# Current_prototype.net
KiCad netlist of a schematic drawn in EAGLE
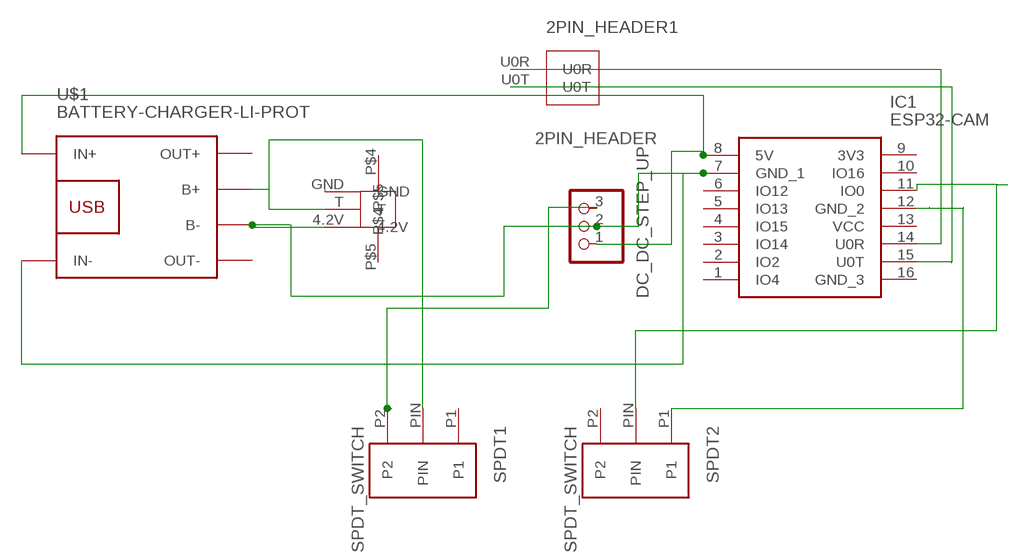
[diagram p0: schematic, sheet 1]

(export (version "E")
  (design (tool "Eeschema 10.0.6"))
  (components
    (comp (ref "2PIN_HEADER1")
      (value "2PIN_HEADER")
      (footprint "eagle-import:2PIN_HEADER")
      (libsource (lib "eagle-import") (part "2PIN_HEADER"))
    )
    (comp (ref "DC_DC_STEP_UP")
      (value "PINHD-1X3")
      (footprint "eagle-import:1X03")
      (libsource (lib "eagle-import") (part "PINHD-1X3"))
    )
    (comp (ref "IC1")
      (value "ESP32-CAM")
      (footprint "eagle-import:ESP32CAM")
      (libsource (lib "eagle-import") (part "ESP32-CAM"))
    )
    (comp (ref "SPDT1")
      (value "SPDT_SWITCH")
      (footprint "eagle-import:SPDT_SWITCH")
      (libsource (lib "eagle-import") (part "SPDT_SWITCH"))
    )
    (comp (ref "SPDT2")
      (value "SPDT_SWITCH")
      (footprint "eagle-import:SPDT_SWITCH")
      (libsource (lib "eagle-import") (part "SPDT_SWITCH"))
    )
    (comp (ref "U$1")
      (value "BATTERY-CHARGER-LI-PROT")
      (footprint "eagle-import:BATTERY-CHARGER-LI-PROT")
      (libsource (lib "eagle-import") (part "BATTERY-CHARGER-LI-PROT"))
    )
    (comp (ref "U$2")
      (value "BATTERY_CONNECTOR")
      (footprint "eagle-import:BATTERY_CONNECTOR")
      (libsource (lib "eagle-import") (part "BATTERY_CONNECTOR"))
    )
  )
  (nets
    (net (code "1") (name "Net-(DC_DC_STEP_UP-Pad3)") (class "Default")
      (node (ref "DC_DC_STEP_UP") (pin "3") (pinfunction "3_3") (pintype "passive"))
      (node (ref "SPDT1") (pin "P2") (pinfunction "P2_P2") (pintype "bidirectional"))
    )
    (net (code "2") (name "Net-(IC1-5V)") (class "Default")
      (node (ref "DC_DC_STEP_UP") (pin "1") (pinfunction "1_1") (pintype "passive"))
      (node (ref "IC1") (pin "8") (pinfunction "5V_8") (pintype "bidirectional"))
      (node (ref "U$1") (pin "IN+") (pinfunction "IN+_IN+") (pintype "bidirectional"))
    )
    (net (code "3") (name "Net-(IC1-GND_1)") (class "Default")
      (node (ref "DC_DC_STEP_UP") (pin "2") (pinfunction "2_2") (pintype "passive"))
      (node (ref "IC1") (pin "7") (pinfunction "GND_1_7") (pintype "bidirectional"))
      (node (ref "U$1") (pin "B-") (pinfunction "B-_B-") (pintype "bidirectional"))
      (node (ref "U$1") (pin "IN-") (pinfunction "IN-_IN-") (pintype "bidirectional"))
      (node (ref "U$2") (pin "4.2V") (pinfunction "4.2V_4.2V") (pintype "bidirectional"))
    )
    (net (code "4") (name "Net-(IC1-GND_2)") (class "Default")
      (node (ref "IC1") (pin "12") (pinfunction "GND_2_12") (pintype "bidirectional"))
      (node (ref "SPDT2") (pin "P1") (pinfunction "P1_P1") (pintype "bidirectional"))
    )
    (net (code "5") (name "Net-(IC1-IO0)") (class "Default")
      (node (ref "IC1") (pin "11") (pinfunction "IO0_11") (pintype "bidirectional"))
      (node (ref "SPDT2") (pin "PIN") (pinfunction "PIN_PIN") (pintype "bidirectional"))
    )
    (net (code "6") (name "Net-(IC1-U0R)") (class "Default")
      (node (ref "2PIN_HEADER1") (pin "U0R") (pinfunction "U0R_U0R") (pintype "bidirectional"))
      (node (ref "IC1") (pin "14") (pinfunction "U0R_14") (pintype "bidirectional"))
    )
    (net (code "7") (name "Net-(IC1-U0T)") (class "Default")
      (node (ref "2PIN_HEADER1") (pin "U0T") (pinfunction "U0T_U0T") (pintype "bidirectional"))
      (node (ref "IC1") (pin "15") (pinfunction "U0T_15") (pintype "bidirectional"))
    )
    (net (code "8") (name "Net-(SPDT1-PadPIN)") (class "Default")
      (node (ref "SPDT1") (pin "PIN") (pinfunction "PIN_PIN") (pintype "bidirectional"))
      (node (ref "U$1") (pin "B+") (pinfunction "B+_B+") (pintype "bidirectional"))
      (node (ref "U$2") (pin "T") (pinfunction "T_T") (pintype "bidirectional"))
    )
    (net (code "9") (name "unconnected-(IC1-3V3-Pad9)") (class "Default")
      (node (ref "IC1") (pin "9") (pinfunction "3V3_9") (pintype "bidirectional"))
    )
    (net (code "10") (name "unconnected-(IC1-GND_3-Pad16)") (class "Default")
      (node (ref "IC1") (pin "16") (pinfunction "GND_3_16") (pintype "bidirectional"))
    )
    (net (code "11") (name "unconnected-(IC1-IO2-Pad2)") (class "Default")
      (node (ref "IC1") (pin "2") (pinfunction "IO2_2") (pintype "bidirectional"))
    )
    (net (code "12") (name "unconnected-(IC1-IO4-Pad1)") (class "Default")
      (node (ref "IC1") (pin "1") (pinfunction "IO4_1") (pintype "bidirectional"))
    )
    (net (code "13") (name "unconnected-(IC1-IO12-Pad6)") (class "Default")
      (node (ref "IC1") (pin "6") (pinfunction "IO12_6") (pintype "bidirectional"))
    )
    (net (code "14") (name "unconnected-(IC1-IO13-Pad5)") (class "Default")
      (node (ref "IC1") (pin "5") (pinfunction "IO13_5") (pintype "bidirectional"))
    )
    (net (code "15") (name "unconnected-(IC1-IO14-Pad3)") (class "Default")
      (node (ref "IC1") (pin "3") (pinfunction "IO14_3") (pintype "bidirectional"))
    )
    (net (code "16") (name "unconnected-(IC1-IO15-Pad4)") (class "Default")
      (node (ref "IC1") (pin "4") (pinfunction "IO15_4") (pintype "bidirectional"))
    )
    (net (code "17") (name "unconnected-(IC1-IO16-Pad10)") (class "Default")
      (node (ref "IC1") (pin "10") (pinfunction "IO16_10") (pintype "bidirectional"))
    )
    (net (code "18") (name "unconnected-(IC1-VCC-Pad13)") (class "Default")
      (node (ref "IC1") (pin "13") (pinfunction "VCC_13") (pintype "bidirectional"))
    )
    (net (code "19") (name "unconnected-(SPDT1-PadP1)") (class "Default")
      (node (ref "SPDT1") (pin "P1") (pinfunction "P1_P1") (pintype "bidirectional"))
    )
    (net (code "20") (name "unconnected-(SPDT2-PadP2)") (class "Default")
      (node (ref "SPDT2") (pin "P2") (pinfunction "P2_P2") (pintype "bidirectional"))
    )
    (net (code "21") (name "unconnected-(U$1-PadOUT+)") (class "Default")
      (node (ref "U$1") (pin "OUT+") (pinfunction "OUT+_OUT+") (pintype "bidirectional"))
    )
    (net (code "22") (name "unconnected-(U$1-PadOUT-)") (class "Default")
      (node (ref "U$1") (pin "OUT-") (pinfunction "OUT-_OUT-") (pintype "bidirectional"))
    )
    (net (code "23") (name "unconnected-(U$2-PadGND)") (class "Default")
      (node (ref "U$2") (pin "GND") (pinfunction "GND_GND") (pintype "bidirectional"))
    )
    (net (code "24") (name "unconnected-(U$2-PadP$4)") (class "Default")
      (node (ref "U$2") (pin "P$4") (pinfunction "P$4_P$4") (pintype "bidirectional"))
    )
    (net (code "25") (name "unconnected-(U$2-PadP$5)") (class "Default")
      (node (ref "U$2") (pin "P$5") (pinfunction "P$5_P$5") (pintype "bidirectional"))
    )
  )
)
